# BitsyOSD-Eagle.net
KiCad netlist of a schematic drawn in EAGLE
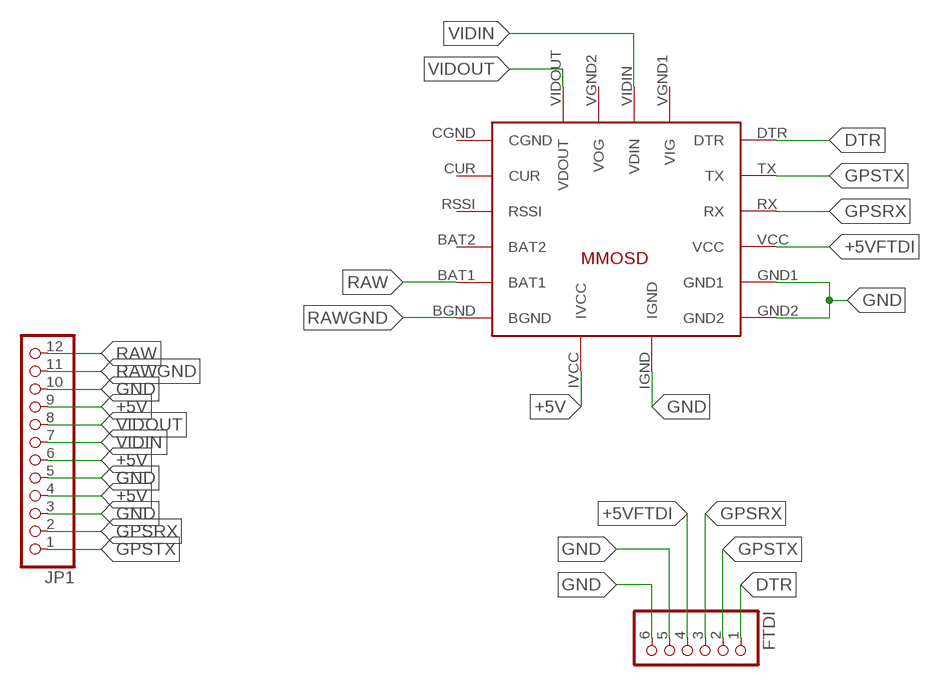
[diagram p0: schematic, sheet 1]

(export (version "E")
  (design (tool "Eeschema 10.0.6"))
  (components
    (comp (ref "FTDI")
      (value "PINHD-1X6")
      (footprint "eagle-import:1X06")
      (libsource (lib "eagle-import") (part "PINHD-1X6"))
    )
    (comp (ref "JP1")
      (value "PINHD-1X12")
      (footprint "eagle-import:1X12")
      (libsource (lib "eagle-import") (part "PINHD-1X12"))
    )
    (comp (ref "U$2")
      (value "MICROMINIMOSDPWR")
      (footprint "eagle-import:MMOSDNVDVID")
      (libsource (lib "eagle-import") (part "MICROMINIMOSDPWR"))
    )
  )
  (nets
    (net (code "1") (name "+5V") (class "Default")
      (node (ref "JP1") (pin "4") (pinfunction "4_4") (pintype "passive"))
      (node (ref "JP1") (pin "6") (pinfunction "6_6") (pintype "passive"))
      (node (ref "JP1") (pin "9") (pinfunction "9_9") (pintype "passive"))
      (node (ref "U$2") (pin "IVCC") (pinfunction "IVCC_IVCC") (pintype "power_in"))
    )
    (net (code "2") (name "+5VFTDI") (class "Default")
      (node (ref "FTDI") (pin "4") (pinfunction "4_4") (pintype "passive"))
      (node (ref "U$2") (pin "VCC") (pinfunction "VCC_VCC") (pintype "power_in"))
    )
    (net (code "3") (name "/BAT2") (class "Default")
      (node (ref "U$2") (pin "BAT2") (pinfunction "BAT2_BAT2") (pintype "power_in"))
    )
    (net (code "4") (name "/CGND") (class "Default")
      (node (ref "U$2") (pin "CGND") (pinfunction "CGND_CGND") (pintype "power_in"))
    )
    (net (code "5") (name "DTR") (class "Default")
      (node (ref "FTDI") (pin "1") (pinfunction "1_1") (pintype "passive"))
      (node (ref "U$2") (pin "DTR") (pinfunction "DTR_DTR") (pintype "bidirectional"))
    )
    (net (code "6") (name "GND") (class "Default")
      (node (ref "FTDI") (pin "5") (pinfunction "5_5") (pintype "passive"))
      (node (ref "FTDI") (pin "6") (pinfunction "6_6") (pintype "passive"))
      (node (ref "JP1") (pin "10") (pinfunction "10_10") (pintype "passive"))
      (node (ref "JP1") (pin "3") (pinfunction "3_3") (pintype "passive"))
      (node (ref "JP1") (pin "5") (pinfunction "5_5") (pintype "passive"))
      (node (ref "U$2") (pin "GND1") (pinfunction "GND1_GND1") (pintype "power_in"))
      (node (ref "U$2") (pin "GND2") (pinfunction "GND2_GND2") (pintype "power_in"))
      (node (ref "U$2") (pin "IGND") (pinfunction "IGND_IGND") (pintype "power_in"))
    )
    (net (code "7") (name "GPSRX") (class "Default")
      (node (ref "FTDI") (pin "3") (pinfunction "3_3") (pintype "passive"))
      (node (ref "JP1") (pin "2") (pinfunction "2_2") (pintype "passive"))
      (node (ref "U$2") (pin "RX") (pinfunction "RX_RX") (pintype "input"))
    )
    (net (code "8") (name "GPSTX") (class "Default")
      (node (ref "FTDI") (pin "2") (pinfunction "2_2") (pintype "passive"))
      (node (ref "JP1") (pin "1") (pinfunction "1_1") (pintype "passive"))
      (node (ref "U$2") (pin "TX") (pinfunction "TX_TX") (pintype "output"))
    )
    (net (code "9") (name "RAW") (class "Default")
      (node (ref "JP1") (pin "12") (pinfunction "12_12") (pintype "passive"))
      (node (ref "U$2") (pin "BAT1") (pinfunction "BAT1_BAT1") (pintype "power_in"))
    )
    (net (code "10") (name "RAWGND") (class "Default")
      (node (ref "JP1") (pin "11") (pinfunction "11_11") (pintype "passive"))
      (node (ref "U$2") (pin "BGND") (pinfunction "BGND_BGND") (pintype "power_in"))
    )
    (net (code "11") (name "VIDIN") (class "Default")
      (node (ref "JP1") (pin "7") (pinfunction "7_7") (pintype "passive"))
      (node (ref "U$2") (pin "VIDIN") (pinfunction "VDIN_VIDIN") (pintype "input"))
    )
    (net (code "12") (name "VIDOUT") (class "Default")
      (node (ref "JP1") (pin "8") (pinfunction "8_8") (pintype "passive"))
      (node (ref "U$2") (pin "VIDOUT") (pinfunction "VDOUT_VIDOUT") (pintype "output"))
    )
    (net (code "13") (name "unconnected-(U$2-PadCUR)") (class "Default")
      (node (ref "U$2") (pin "CUR") (pinfunction "CUR_CUR") (pintype "bidirectional"))
    )
    (net (code "14") (name "unconnected-(U$2-PadRSSI)") (class "Default")
      (node (ref "U$2") (pin "RSSI") (pinfunction "RSSI_RSSI") (pintype "bidirectional"))
    )
    (net (code "15") (name "unconnected-(U$2-VIG-PadVGND1)") (class "Default")
      (node (ref "U$2") (pin "VGND1") (pinfunction "VIG_VGND1") (pintype "input"))
    )
    (net (code "16") (name "unconnected-(U$2-VOG-PadVGND2)") (class "Default")
      (node (ref "U$2") (pin "VGND2") (pinfunction "VOG_VGND2") (pintype "output"))
    )
  )
)
